# HAT.net
KiCad netlist of a schematic drawn in EAGLE
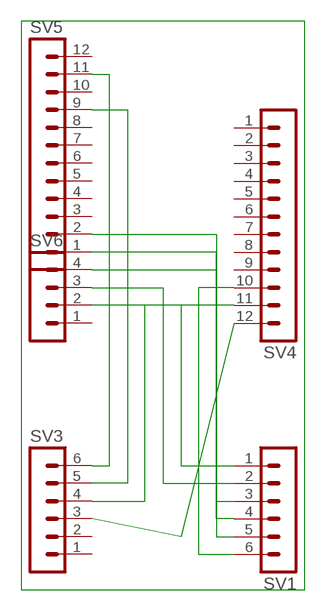
[diagram p0: schematic, sheet 1]

(export (version "E")
  (design (tool "Eeschema 10.0.6"))
  (components
    (comp (ref "SV1")
      (value "MA06-1")
      (footprint "eagle-import:MA06-1")
      (libsource (lib "eagle-import") (part "MA06-1"))
    )
    (comp (ref "SV3")
      (value "MA06-1")
      (footprint "eagle-import:MA06-1")
      (libsource (lib "eagle-import") (part "MA06-1"))
    )
    (comp (ref "SV4")
      (value "MA12-1")
      (footprint "eagle-import:MA12-1")
      (libsource (lib "eagle-import") (part "MA12-1"))
    )
    (comp (ref "SV5")
      (value "MA12-1")
      (footprint "eagle-import:MA12-1")
      (libsource (lib "eagle-import") (part "MA12-1"))
    )
    (comp (ref "SV6")
      (value "MA04-1")
      (footprint "eagle-import:MA04-1")
      (libsource (lib "eagle-import") (part "MA04-1"))
    )
  )
  (nets
    (net (code "1") (name "Net-(SV1-Pad1)") (class "Default")
      (node (ref "SV1") (pin "1") (pinfunction "1_1") (pintype "passive"))
      (node (ref "SV6") (pin "2") (pinfunction "2_2") (pintype "passive"))
    )
    (net (code "2") (name "Net-(SV1-Pad2)") (class "Default")
      (node (ref "SV1") (pin "2") (pinfunction "2_2") (pintype "passive"))
      (node (ref "SV6") (pin "3") (pinfunction "3_3") (pintype "passive"))
    )
    (net (code "3") (name "Net-(SV1-Pad3)") (class "Default")
      (node (ref "SV1") (pin "3") (pinfunction "3_3") (pintype "passive"))
      (node (ref "SV6") (pin "4") (pinfunction "4_4") (pintype "passive"))
    )
    (net (code "4") (name "Net-(SV1-Pad4)") (class "Default")
      (node (ref "SV1") (pin "4") (pinfunction "4_4") (pintype "passive"))
      (node (ref "SV5") (pin "1") (pinfunction "1_1") (pintype "passive"))
    )
    (net (code "5") (name "Net-(SV1-Pad5)") (class "Default")
      (node (ref "SV1") (pin "5") (pinfunction "5_5") (pintype "passive"))
      (node (ref "SV5") (pin "2") (pinfunction "2_2") (pintype "passive"))
    )
    (net (code "6") (name "Net-(SV1-Pad6)") (class "Default")
      (node (ref "SV1") (pin "6") (pinfunction "6_6") (pintype "passive"))
      (node (ref "SV4") (pin "10") (pinfunction "10_10") (pintype "passive"))
    )
    (net (code "7") (name "Net-(SV3-Pad3)") (class "Default")
      (node (ref "SV3") (pin "3") (pinfunction "3_3") (pintype "passive"))
      (node (ref "SV4") (pin "12") (pinfunction "12_12") (pintype "passive"))
    )
    (net (code "8") (name "Net-(SV3-Pad4)") (class "Default")
      (node (ref "SV3") (pin "4") (pinfunction "4_4") (pintype "passive"))
      (node (ref "SV4") (pin "11") (pinfunction "11_11") (pintype "passive"))
    )
    (net (code "9") (name "Net-(SV3-Pad5)") (class "Default")
      (node (ref "SV3") (pin "5") (pinfunction "5_5") (pintype "passive"))
      (node (ref "SV5") (pin "9") (pinfunction "9_9") (pintype "passive"))
    )
    (net (code "10") (name "Net-(SV3-Pad6)") (class "Default")
      (node (ref "SV3") (pin "6") (pinfunction "6_6") (pintype "passive"))
      (node (ref "SV5") (pin "11") (pinfunction "11_11") (pintype "passive"))
    )
    (net (code "11") (name "unconnected-(SV3-Pad1)") (class "Default")
      (node (ref "SV3") (pin "1") (pinfunction "1_1") (pintype "passive"))
    )
    (net (code "12") (name "unconnected-(SV3-Pad2)") (class "Default")
      (node (ref "SV3") (pin "2") (pinfunction "2_2") (pintype "passive"))
    )
    (net (code "13") (name "unconnected-(SV4-Pad1)") (class "Default")
      (node (ref "SV4") (pin "1") (pinfunction "1_1") (pintype "passive"))
    )
    (net (code "14") (name "unconnected-(SV4-Pad2)") (class "Default")
      (node (ref "SV4") (pin "2") (pinfunction "2_2") (pintype "passive"))
    )
    (net (code "15") (name "unconnected-(SV4-Pad3)") (class "Default")
      (node (ref "SV4") (pin "3") (pinfunction "3_3") (pintype "passive"))
    )
    (net (code "16") (name "unconnected-(SV4-Pad4)") (class "Default")
      (node (ref "SV4") (pin "4") (pinfunction "4_4") (pintype "passive"))
    )
    (net (code "17") (name "unconnected-(SV4-Pad5)") (class "Default")
      (node (ref "SV4") (pin "5") (pinfunction "5_5") (pintype "passive"))
    )
    (net (code "18") (name "unconnected-(SV4-Pad6)") (class "Default")
      (node (ref "SV4") (pin "6") (pinfunction "6_6") (pintype "passive"))
    )
    (net (code "19") (name "unconnected-(SV4-Pad7)") (class "Default")
      (node (ref "SV4") (pin "7") (pinfunction "7_7") (pintype "passive"))
    )
    (net (code "20") (name "unconnected-(SV4-Pad8)") (class "Default")
      (node (ref "SV4") (pin "8") (pinfunction "8_8") (pintype "passive"))
    )
    (net (code "21") (name "unconnected-(SV4-Pad9)") (class "Default")
      (node (ref "SV4") (pin "9") (pinfunction "9_9") (pintype "passive"))
    )
    (net (code "22") (name "unconnected-(SV5-Pad3)") (class "Default")
      (node (ref "SV5") (pin "3") (pinfunction "3_3") (pintype "passive"))
    )
    (net (code "23") (name "unconnected-(SV5-Pad4)") (class "Default")
      (node (ref "SV5") (pin "4") (pinfunction "4_4") (pintype "passive"))
    )
    (net (code "24") (name "unconnected-(SV5-Pad5)") (class "Default")
      (node (ref "SV5") (pin "5") (pinfunction "5_5") (pintype "passive"))
    )
    (net (code "25") (name "unconnected-(SV5-Pad6)") (class "Default")
      (node (ref "SV5") (pin "6") (pinfunction "6_6") (pintype "passive"))
    )
    (net (code "26") (name "unconnected-(SV5-Pad7)") (class "Default")
      (node (ref "SV5") (pin "7") (pinfunction "7_7") (pintype "passive"))
    )
    (net (code "27") (name "unconnected-(SV5-Pad8)") (class "Default")
      (node (ref "SV5") (pin "8") (pinfunction "8_8") (pintype "passive"))
    )
    (net (code "28") (name "unconnected-(SV5-Pad10)") (class "Default")
      (node (ref "SV5") (pin "10") (pinfunction "10_10") (pintype "passive"))
    )
    (net (code "29") (name "unconnected-(SV5-Pad12)") (class "Default")
      (node (ref "SV5") (pin "12") (pinfunction "12_12") (pintype "passive"))
    )
    (net (code "30") (name "unconnected-(SV6-Pad1)") (class "Default")
      (node (ref "SV6") (pin "1") (pinfunction "1_1") (pintype "passive"))
    )
  )
)
